# 0_cpu_interface.net
KiCad netlist of a schematic drawn in EAGLE
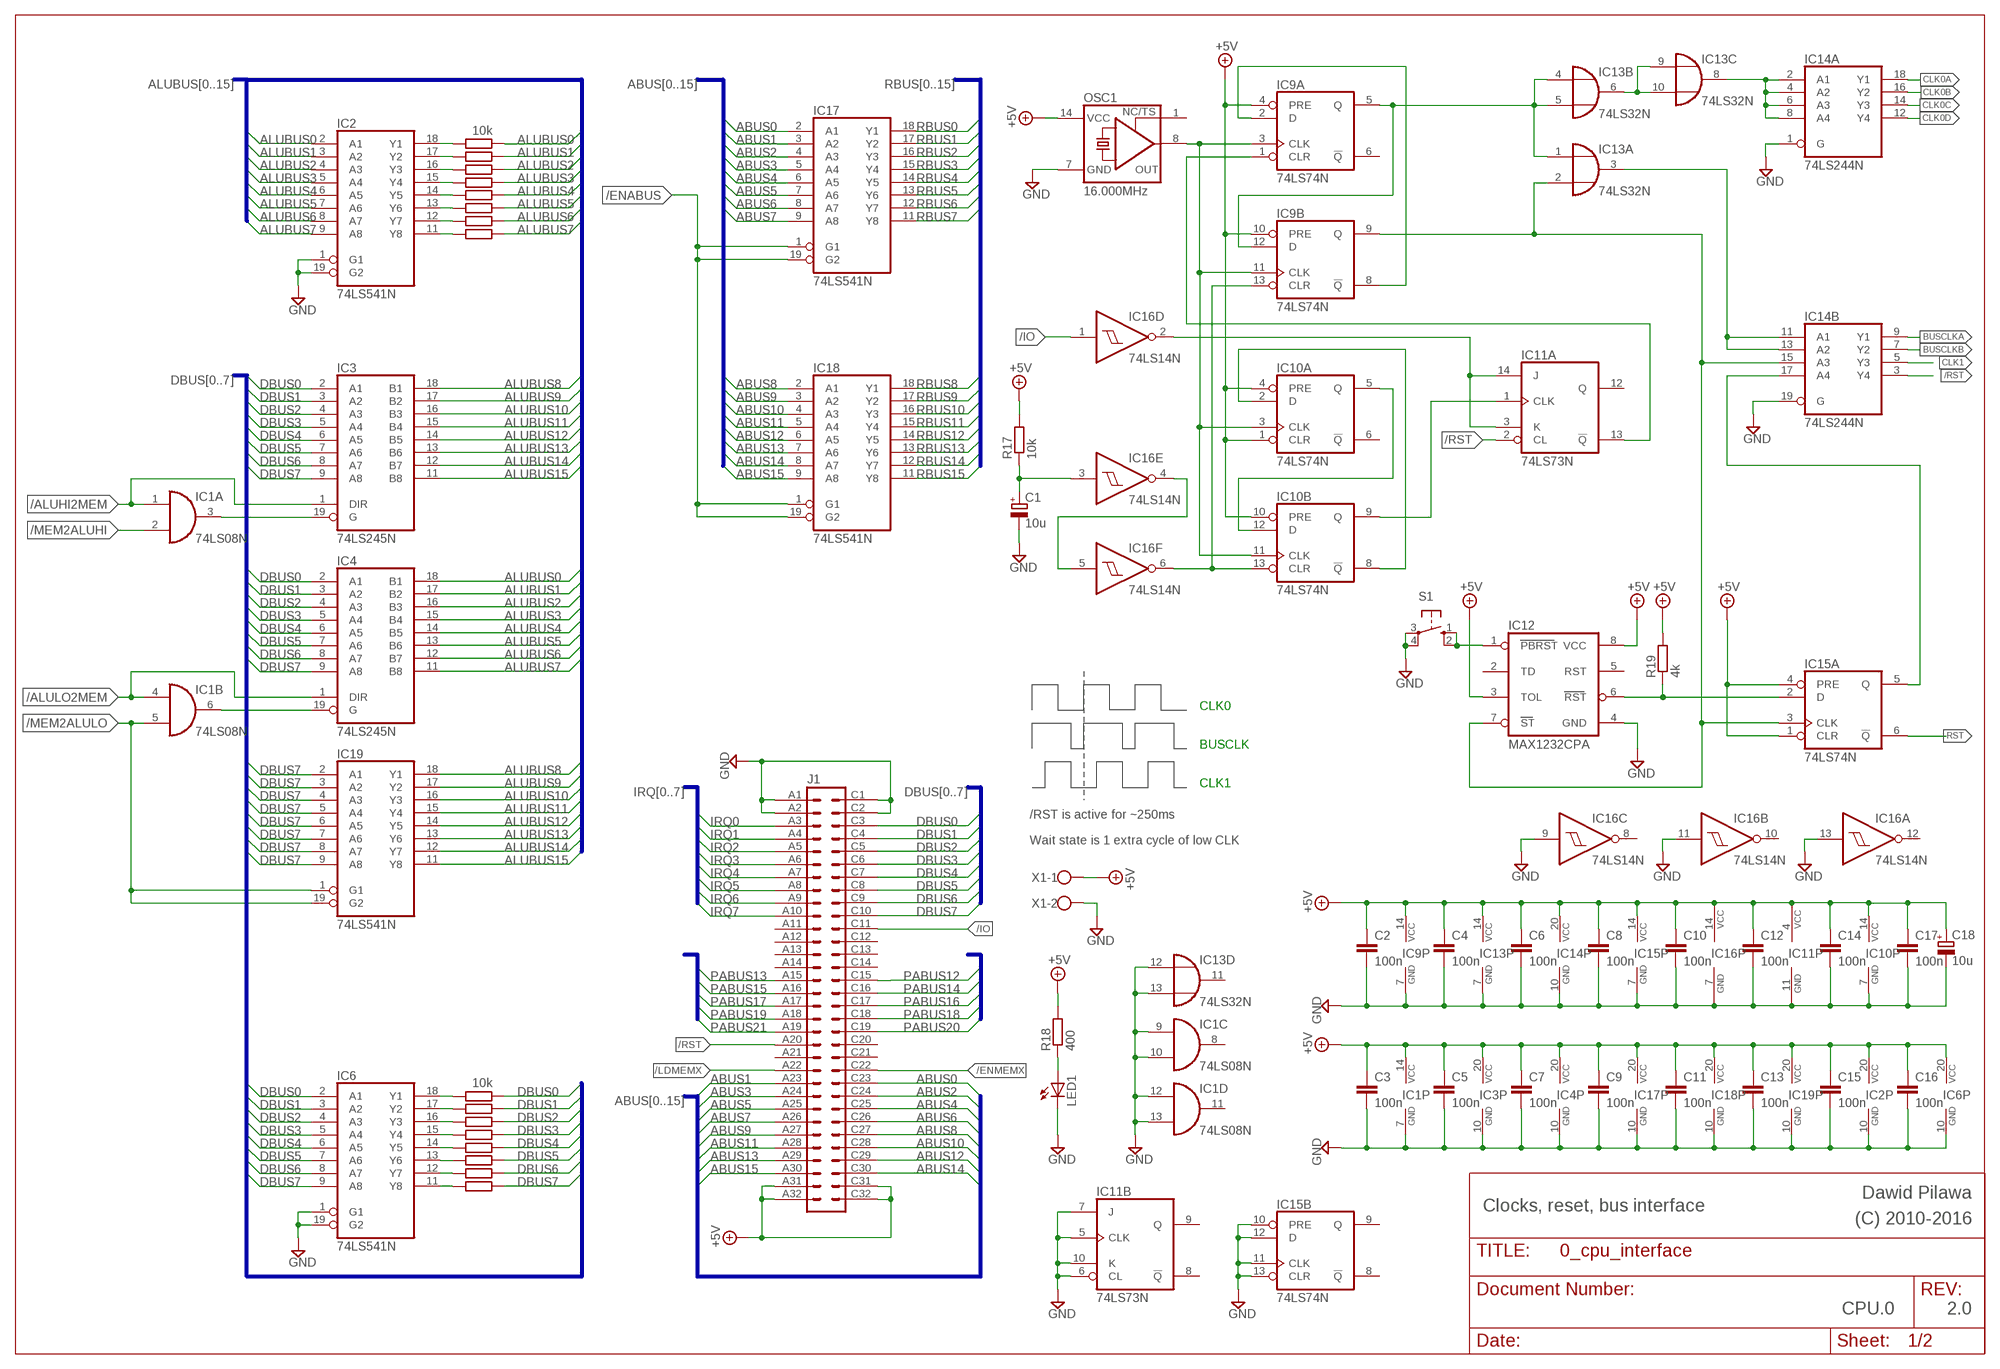
[diagram p0: schematic, sheet 1]
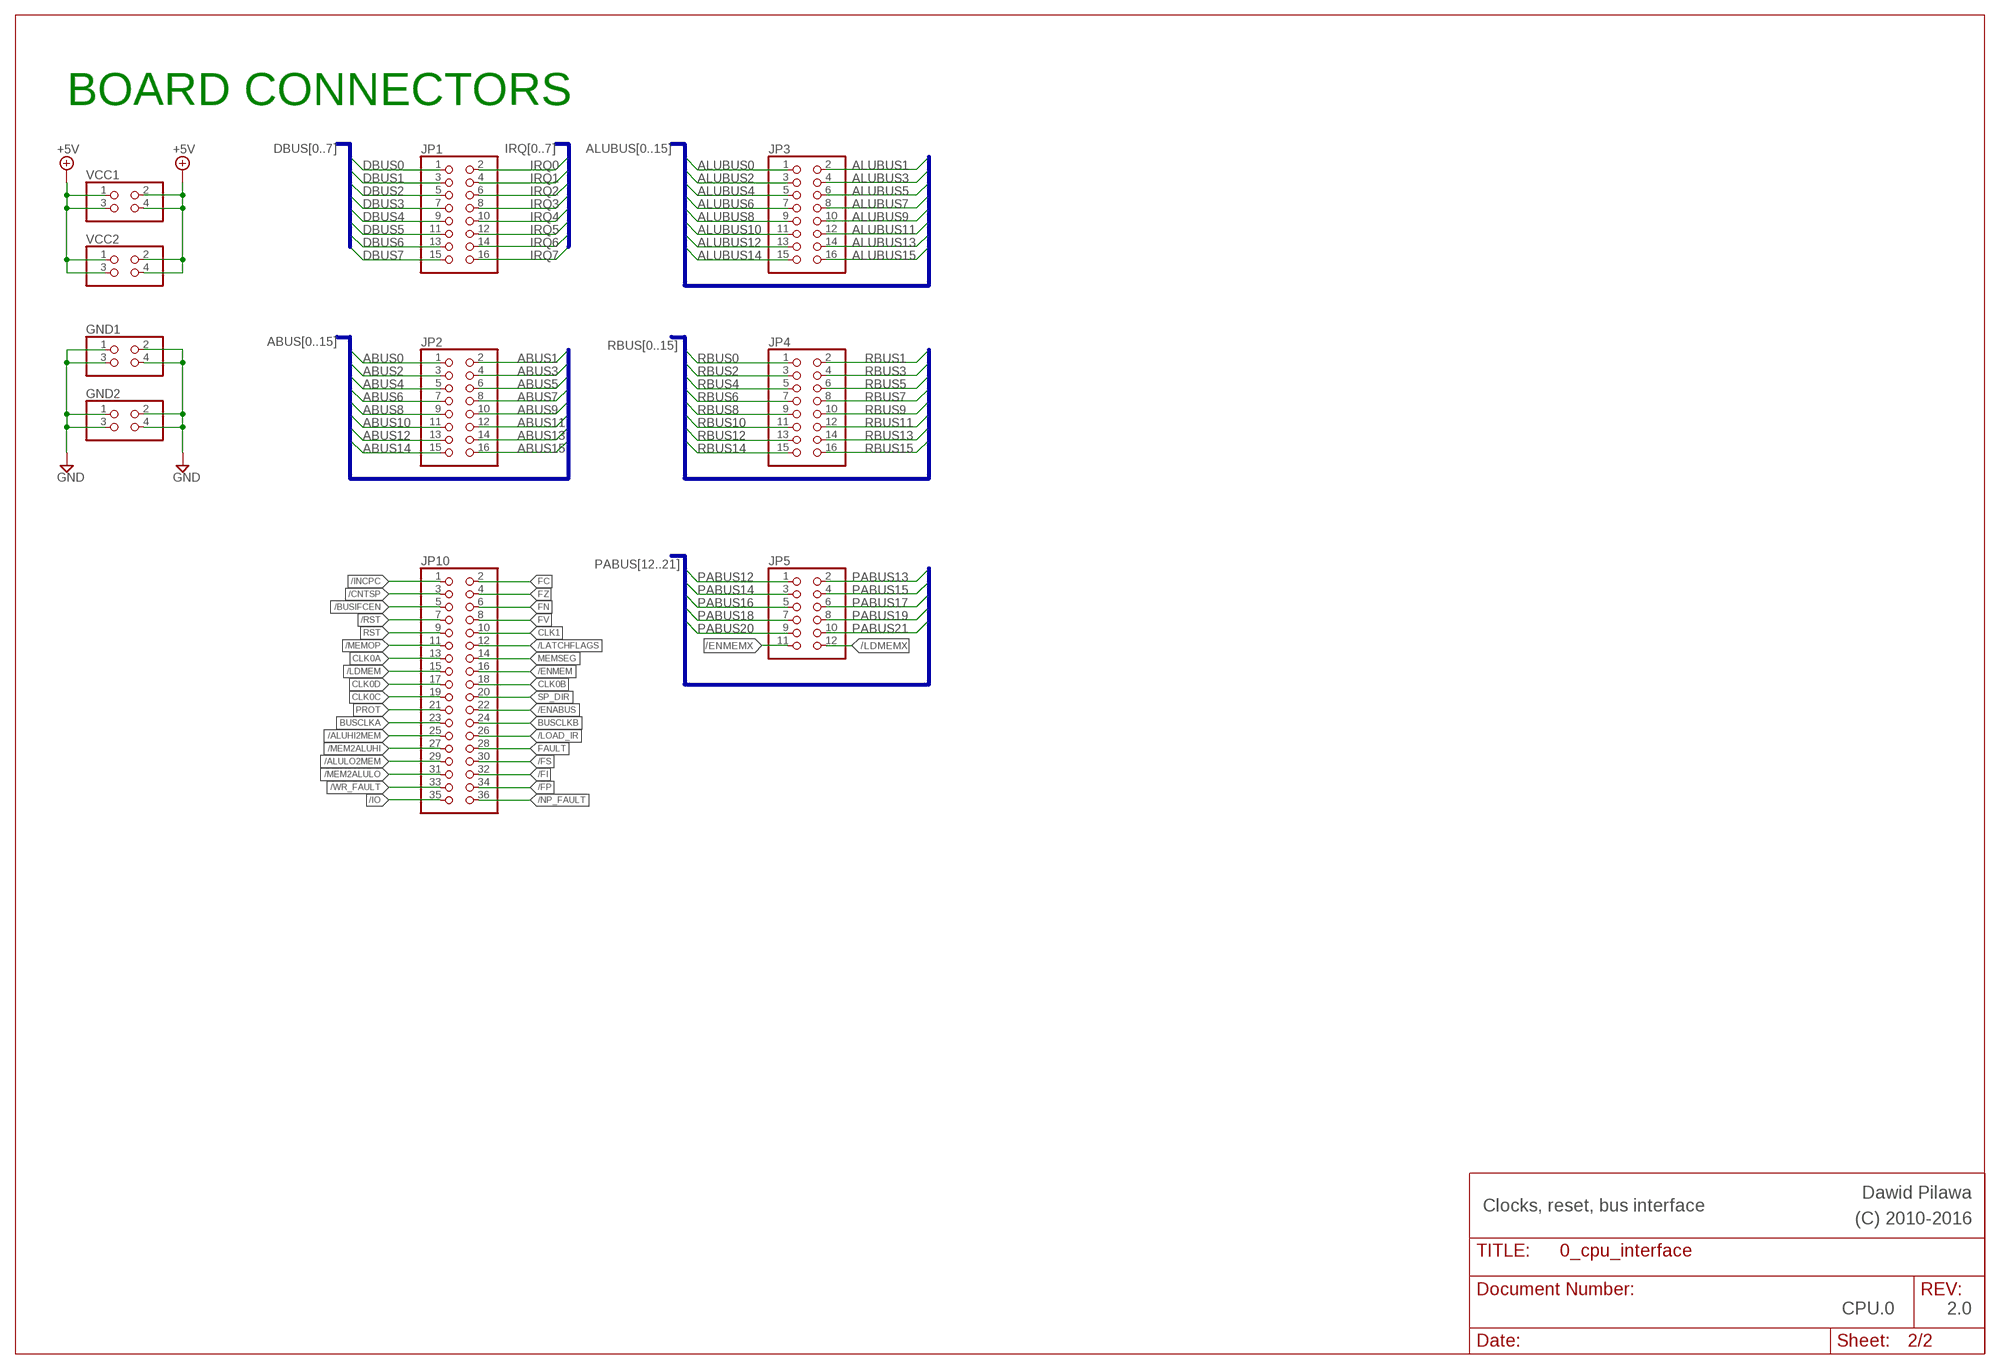
[diagram p1: schematic, sheet 2]

(export (version "E")
  (design (tool "Eeschema 10.0.6"))
  (components
    (comp (ref "C1")
      (value "10u")
      (footprint "eagle-import:E2,5-5")
      (libsource (lib "eagle-import") (part "CPOL-EUE2.5-5"))
    )
    (comp (ref "C2")
      (value "100n")
      (footprint "eagle-import:C050-024X044")
      (libsource (lib "eagle-import") (part "C-EU050-024X044"))
    )
    (comp (ref "C3")
      (value "100n")
      (footprint "eagle-import:C050-024X044")
      (libsource (lib "eagle-import") (part "C-EU050-024X044"))
    )
    (comp (ref "C4")
      (value "100n")
      (footprint "eagle-import:C050-024X044")
      (libsource (lib "eagle-import") (part "C-EU050-024X044"))
    )
    (comp (ref "C5")
      (value "100n")
      (footprint "eagle-import:C050-024X044")
      (libsource (lib "eagle-import") (part "C-EU050-024X044"))
    )
    (comp (ref "C6")
      (value "100n")
      (footprint "eagle-import:C050-024X044")
      (libsource (lib "eagle-import") (part "C-EU050-024X044"))
    )
    (comp (ref "C7")
      (value "100n")
      (footprint "eagle-import:C050-024X044")
      (libsource (lib "eagle-import") (part "C-EU050-024X044"))
    )
    (comp (ref "C8")
      (value "100n")
      (footprint "eagle-import:C050-024X044")
      (libsource (lib "eagle-import") (part "C-EU050-024X044"))
    )
    (comp (ref "C9")
      (value "100n")
      (footprint "eagle-import:C050-024X044")
      (libsource (lib "eagle-import") (part "C-EU050-024X044"))
    )
    (comp (ref "C10")
      (value "100n")
      (footprint "eagle-import:C050-024X044")
      (libsource (lib "eagle-import") (part "C-EU050-024X044"))
    )
    (comp (ref "C11")
      (value "100n")
      (footprint "eagle-import:C050-024X044")
      (libsource (lib "eagle-import") (part "C-EU050-024X044"))
    )
    (comp (ref "C12")
      (value "100n")
      (footprint "eagle-import:C050-024X044")
      (libsource (lib "eagle-import") (part "C-EU050-024X044"))
    )
    (comp (ref "C13")
      (value "100n")
      (footprint "eagle-import:C050-024X044")
      (libsource (lib "eagle-import") (part "C-EU050-024X044"))
    )
    (comp (ref "C14")
      (value "100n")
      (footprint "eagle-import:C050-024X044")
      (libsource (lib "eagle-import") (part "C-EU050-024X044"))
    )
    (comp (ref "C15")
      (value "100n")
      (footprint "eagle-import:C050-024X044")
      (libsource (lib "eagle-import") (part "C-EU050-024X044"))
    )
    (comp (ref "C16")
      (value "100n")
      (footprint "eagle-import:C050-024X044")
      (libsource (lib "eagle-import") (part "C-EU050-024X044"))
    )
    (comp (ref "C17")
      (value "100n")
      (footprint "eagle-import:C050-024X044")
      (libsource (lib "eagle-import") (part "C-EU050-024X044"))
    )
    (comp (ref "C18")
      (value "10u")
      (footprint "eagle-import:E2,5-6")
      (libsource (lib "eagle-import") (part "CPOL-EUE2.5-6"))
    )
    (comp (ref "IC1")
      (value "74LS08N")
      (footprint "eagle-import:DIL14")
      (libsource (lib "eagle-import") (part "7408NLS"))
    )
    (comp (ref "IC2")
      (value "74LS541N")
      (footprint "eagle-import:DIL20")
      (libsource (lib "eagle-import") (part "74541NLS"))
    )
    (comp (ref "IC3")
      (value "74LS245N")
      (footprint "eagle-import:DIL20")
      (libsource (lib "eagle-import") (part "74245NLS"))
    )
    (comp (ref "IC4")
      (value "74LS245N")
      (footprint "eagle-import:DIL20")
      (libsource (lib "eagle-import") (part "74245NLS"))
    )
    (comp (ref "IC6")
      (value "74LS541N")
      (footprint "eagle-import:DIL20")
      (libsource (lib "eagle-import") (part "74541NLS"))
    )
    (comp (ref "IC9")
      (value "74LS74N")
      (footprint "eagle-import:DIL14")
      (libsource (lib "eagle-import") (part "7474NLS"))
    )
    (comp (ref "IC10")
      (value "74LS74N")
      (footprint "eagle-import:DIL14")
      (libsource (lib "eagle-import") (part "7474NLS"))
    )
    (comp (ref "IC11")
      (value "74LS73N")
      (footprint "eagle-import:DIL14")
      (libsource (lib "eagle-import") (part "7473NLS"))
    )
    (comp (ref "IC12")
      (value "MAX1232CPA")
      (footprint "eagle-import:DIL08")
      (libsource (lib "eagle-import") (part "MAX1232CPA"))
    )
    (comp (ref "IC13")
      (value "74LS32N")
      (footprint "eagle-import:DIL14")
      (libsource (lib "eagle-import") (part "7432NLS"))
    )
    (comp (ref "IC14")
      (value "74LS244N")
      (footprint "eagle-import:DIL20")
      (libsource (lib "eagle-import") (part "74244NLS"))
    )
    (comp (ref "IC15")
      (value "74LS74N")
      (footprint "eagle-import:DIL14")
      (libsource (lib "eagle-import") (part "7474NLS"))
    )
    (comp (ref "IC16")
      (value "74LS14N")
      (footprint "eagle-import:DIL14")
      (libsource (lib "eagle-import") (part "7414NLS"))
    )
    (comp (ref "IC17")
      (value "74LS541N")
      (footprint "eagle-import:DIL20")
      (libsource (lib "eagle-import") (part "74541NLS"))
    )
    (comp (ref "IC18")
      (value "74LS541N")
      (footprint "eagle-import:DIL20")
      (libsource (lib "eagle-import") (part "74541NLS"))
    )
    (comp (ref "IC19")
      (value "74LS541N")
      (footprint "eagle-import:DIL20")
      (libsource (lib "eagle-import") (part "74541NLS"))
    )
    (comp (ref "J1")
      (value "VG64B")
      (footprint "eagle-import:VG64B")
      (libsource (lib "eagle-import") (part "VG64B"))
    )
    (comp (ref "LED1")
      (value "LED5MM")
      (footprint "eagle-import:LED5MM")
      (libsource (lib "eagle-import") (part "LED5MM"))
    )
    (comp (ref "OSC1")
      (value "16.000MHz")
      (footprint "eagle-import:DIL14S")
      (libsource (lib "eagle-import") (part "XO-14"))
    )
    (comp (ref "R1")
      (value "10k")
      (footprint "eagle-import:0204_7")
      (libsource (lib "eagle-import") (part "R-EU_0204/7"))
    )
    (comp (ref "R2")
      (value "R-EU_0204/7")
      (footprint "eagle-import:0204_7")
      (libsource (lib "eagle-import") (part "R-EU_0204/7"))
    )
    (comp (ref "R3")
      (value "R-EU_0204/7")
      (footprint "eagle-import:0204_7")
      (libsource (lib "eagle-import") (part "R-EU_0204/7"))
    )
    (comp (ref "R4")
      (value "R-EU_0204/7")
      (footprint "eagle-import:0204_7")
      (libsource (lib "eagle-import") (part "R-EU_0204/7"))
    )
    (comp (ref "R5")
      (value "R-EU_0204/7")
      (footprint "eagle-import:0204_7")
      (libsource (lib "eagle-import") (part "R-EU_0204/7"))
    )
    (comp (ref "R6")
      (value "R-EU_0204/7")
      (footprint "eagle-import:0204_7")
      (libsource (lib "eagle-import") (part "R-EU_0204/7"))
    )
    (comp (ref "R7")
      (value "R-EU_0204/7")
      (footprint "eagle-import:0204_7")
      (libsource (lib "eagle-import") (part "R-EU_0204/7"))
    )
    (comp (ref "R8")
      (value "R-EU_0204/7")
      (footprint "eagle-import:0204_7")
      (libsource (lib "eagle-import") (part "R-EU_0204/7"))
    )
    (comp (ref "R9")
      (value "10k")
      (footprint "eagle-import:0204_7")
      (libsource (lib "eagle-import") (part "R-EU_0204/7"))
    )
    (comp (ref "R10")
      (value "R-EU_0204/7")
      (footprint "eagle-import:0204_7")
      (libsource (lib "eagle-import") (part "R-EU_0204/7"))
    )
    (comp (ref "R11")
      (value "R-EU_0204/7")
      (footprint "eagle-import:0204_7")
      (libsource (lib "eagle-import") (part "R-EU_0204/7"))
    )
    (comp (ref "R12")
      (value "R-EU_0204/7")
      (footprint "eagle-import:0204_7")
      (libsource (lib "eagle-import") (part "R-EU_0204/7"))
    )
    (comp (ref "R13")
      (value "R-EU_0204/7")
      (footprint "eagle-import:0204_7")
      (libsource (lib "eagle-import") (part "R-EU_0204/7"))
    )
    (comp (ref "R14")
      (value "R-EU_0204/7")
      (footprint "eagle-import:0204_7")
      (libsource (lib "eagle-import") (part "R-EU_0204/7"))
    )
    (comp (ref "R15")
      (value "R-EU_0204/7")
      (footprint "eagle-import:0204_7")
      (libsource (lib "eagle-import") (part "R-EU_0204/7"))
    )
    (comp (ref "R16")
      (value "R-EU_0204/7")
      (footprint "eagle-import:0204_7")
      (libsource (lib "eagle-import") (part "R-EU_0204/7"))
    )
    (comp (ref "R17")
      (value "10k")
      (footprint "eagle-import:0204_7")
      (libsource (lib "eagle-import") (part "R-EU_0204/7"))
    )
    (comp (ref "R18")
      (value "400")
      (footprint "eagle-import:0204_7")
      (libsource (lib "eagle-import") (part "R-EU_0204/7"))
    )
    (comp (ref "R19")
      (value "4k")
      (footprint "eagle-import:0204_7")
      (libsource (lib "eagle-import") (part "R-EU_0204/7"))
    )
    (comp (ref "S1")
      (value "10-XX")
      (footprint "eagle-import:B3F-10XX")
      (fields (field (name "MPN") "B3F-1000"))
      (libsource (lib "eagle-import") (part "10-XX"))
    )
    (comp (ref "X1")
      (value "W237-102")
      (footprint "eagle-import:W237-102")
      (fields (field (name "MPN") "237-102"))
      (libsource (lib "eagle-import") (part "W237-102"))
    )
    (comp (ref "GND1")
      (value "PINHD-2X2")
      (footprint "eagle-import:2X02")
      (libsource (lib "eagle-import") (part "PINHD-2X2"))
    )
    (comp (ref "GND2")
      (value "PINHD-2X2")
      (footprint "eagle-import:2X02")
      (libsource (lib "eagle-import") (part "PINHD-2X2"))
    )
    (comp (ref "JP1")
      (value "PINHD-2X8")
      (footprint "eagle-import:2X08")
      (libsource (lib "eagle-import") (part "PINHD-2X8"))
    )
    (comp (ref "JP2")
      (value "PINHD-2X8")
      (footprint "eagle-import:2X08")
      (libsource (lib "eagle-import") (part "PINHD-2X8"))
    )
    (comp (ref "JP3")
      (value "PINHD-2X8")
      (footprint "eagle-import:2X08")
      (libsource (lib "eagle-import") (part "PINHD-2X8"))
    )
    (comp (ref "JP4")
      (value "PINHD-2X8")
      (footprint "eagle-import:2X08")
      (libsource (lib "eagle-import") (part "PINHD-2X8"))
    )
    (comp (ref "JP5")
      (value "PINHD-2X6")
      (footprint "eagle-import:2X06")
      (libsource (lib "eagle-import") (part "PINHD-2X6"))
    )
    (comp (ref "JP10")
      (value "PINHD-2X18")
      (footprint "eagle-import:2X18")
      (libsource (lib "eagle-import") (part "PINHD-2X18"))
    )
    (comp (ref "VCC1")
      (value "PINHD-2X2")
      (footprint "eagle-import:2X02")
      (libsource (lib "eagle-import") (part "PINHD-2X2"))
    )
    (comp (ref "VCC2")
      (value "PINHD-2X2")
      (footprint "eagle-import:2X02")
      (libsource (lib "eagle-import") (part "PINHD-2X2"))
    )
  )
  (nets
    (net (code "1") (name "+5V") (class "Default")
      (node (ref "C10") (pin "1") (pinfunction "1_1") (pintype "passive"))
      (node (ref "C11") (pin "1") (pinfunction "1_1") (pintype "passive"))
      (node (ref "C12") (pin "1") (pinfunction "1_1") (pintype "passive"))
      (node (ref "C13") (pin "1") (pinfunction "1_1") (pintype "passive"))
      (node (ref "C14") (pin "1") (pinfunction "1_1") (pintype "passive"))
      (node (ref "C15") (pin "1") (pinfunction "1_1") (pintype "passive"))
      (node (ref "C16") (pin "1") (pinfunction "1_1") (pintype "passive"))
      (node (ref "C17") (pin "1") (pinfunction "1_1") (pintype "passive"))
      (node (ref "C18") (pin "+") (pinfunction "+_+") (pintype "passive"))
      (node (ref "C2") (pin "1") (pinfunction "1_1") (pintype "passive"))
      (node (ref "C3") (pin "1") (pinfunction "1_1") (pintype "passive"))
      (node (ref "C4") (pin "1") (pinfunction "1_1") (pintype "passive"))
      (node (ref "C5") (pin "1") (pinfunction "1_1") (pintype "passive"))
      (node (ref "C6") (pin "1") (pinfunction "1_1") (pintype "passive"))
      (node (ref "C7") (pin "1") (pinfunction "1_1") (pintype "passive"))
      (node (ref "C8") (pin "1") (pinfunction "1_1") (pintype "passive"))
      (node (ref "C9") (pin "1") (pinfunction "1_1") (pintype "passive"))
      (node (ref "IC1") (pin "14") (pinfunction "VCC_14") (pintype "power_in"))
      (node (ref "IC10") (pin "1") (pinfunction "CLR_1") (pintype "input"))
      (node (ref "IC10") (pin "10") (pinfunction "PRE_10") (pintype "input"))
      (node (ref "IC10") (pin "14") (pinfunction "VCC_14") (pintype "power_in"))
      (node (ref "IC10") (pin "4") (pinfunction "PRE_4") (pintype "input"))
      (node (ref "IC11") (pin "4") (pinfunction "VCC_4") (pintype "power_in"))
      (node (ref "IC12") (pin "3") (pinfunction "TOL_3") (pintype "input"))
      (node (ref "IC12") (pin "8") (pinfunction "VCC_8") (pintype "power_in"))
      (node (ref "IC13") (pin "14") (pinfunction "VCC_14") (pintype "power_in"))
      (node (ref "IC14") (pin "20") (pinfunction "VCC_20") (pintype "power_in"))
      (node (ref "IC15") (pin "1") (pinfunction "CLR_1") (pintype "input"))
      (node (ref "IC15") (pin "14") (pinfunction "VCC_14") (pintype "power_in"))
      (node (ref "IC15") (pin "4") (pinfunction "PRE_4") (pintype "input"))
      (node (ref "IC16") (pin "14") (pinfunction "VCC_14") (pintype "power_in"))
      (node (ref "IC17") (pin "20") (pinfunction "VCC_20") (pintype "power_in"))
      (node (ref "IC18") (pin "20") (pinfunction "VCC_20") (pintype "power_in"))
      (node (ref "IC19") (pin "20") (pinfunction "VCC_20") (pintype "power_in"))
      (node (ref "IC2") (pin "20") (pinfunction "VCC_20") (pintype "power_in"))
      (node (ref "IC3") (pin "20") (pinfunction "VCC_20") (pintype "power_in"))
      (node (ref "IC4") (pin "20") (pinfunction "VCC_20") (pintype "power_in"))
      (node (ref "IC6") (pin "20") (pinfunction "VCC_20") (pintype "power_in"))
      (node (ref "IC9") (pin "10") (pinfunction "PRE_10") (pintype "input"))
      (node (ref "IC9") (pin "14") (pinfunction "VCC_14") (pintype "power_in"))
      (node (ref "IC9") (pin "4") (pinfunction "PRE_4") (pintype "input"))
      (node (ref "J1") (pin "A31") (pinfunction "A31_A31") (pintype "passive"))
      (node (ref "J1") (pin "A32") (pinfunction "A32_A32") (pintype "passive"))
      (node (ref "J1") (pin "C31") (pinfunction "C31_C31") (pintype "passive"))
      (node (ref "J1") (pin "C32") (pinfunction "C32_C32") (pintype "passive"))
      (node (ref "OSC1") (pin "14") (pinfunction "VCC_14") (pintype "power_in"))
      (node (ref "R17") (pin "2") (pinfunction "2_2") (pintype "passive"))
      (node (ref "R18") (pin "2") (pinfunction "2_2") (pintype "passive"))
      (node (ref "R19") (pin "2") (pinfunction "2_2") (pintype "passive"))
      (node (ref "VCC1") (pin "1") (pinfunction "1_1") (pintype "passive"))
      (node (ref "VCC1") (pin "2") (pinfunction "2_2") (pintype "passive"))
      (node (ref "VCC1") (pin "3") (pinfunction "3_3") (pintype "passive"))
      (node (ref "VCC1") (pin "4") (pinfunction "4_4") (pintype "passive"))
      (node (ref "VCC2") (pin "1") (pinfunction "1_1") (pintype "passive"))
      (node (ref "VCC2") (pin "2") (pinfunction "2_2") (pintype "passive"))
      (node (ref "VCC2") (pin "3") (pinfunction "3_3") (pintype "passive"))
      (node (ref "VCC2") (pin "4") (pinfunction "4_4") (pintype "passive"))
      (node (ref "X1") (pin "1") (pinfunction "KL_1") (pintype "passive"))
    )
    (net (code "14") (name "ABUS0") (class "Default")
      (node (ref "IC17") (pin "2") (pinfunction "A1_2") (pintype "input"))
      (node (ref "J1") (pin "C23") (pinfunction "C23_C23") (pintype "passive"))
      (node (ref "JP2") (pin "1") (pinfunction "1_1") (pintype "passive"))
    )
    (net (code "15") (name "ABUS1") (class "Default")
      (node (ref "IC17") (pin "3") (pinfunction "A2_3") (pintype "input"))
      (node (ref "J1") (pin "A23") (pinfunction "A23_A23") (pintype "passive"))
      (node (ref "JP2") (pin "2") (pinfunction "2_2") (pintype "passive"))
    )
    (net (code "16") (name "ABUS2") (class "Default")
      (node (ref "IC17") (pin "4") (pinfunction "A3_4") (pintype "input"))
      (node (ref "J1") (pin "C24") (pinfunction "C24_C24") (pintype "passive"))
      (node (ref "JP2") (pin "3") (pinfunction "3_3") (pintype "passive"))
    )
    (net (code "17") (name "ABUS3") (class "Default")
      (node (ref "IC17") (pin "5") (pinfunction "A4_5") (pintype "input"))
      (node (ref "J1") (pin "A24") (pinfunction "A24_A24") (pintype "passive"))
      (node (ref "JP2") (pin "4") (pinfunction "4_4") (pintype "passive"))
    )
    (net (code "18") (name "ABUS4") (class "Default")
      (node (ref "IC17") (pin "6") (pinfunction "A5_6") (pintype "input"))
      (node (ref "J1") (pin "C25") (pinfunction "C25_C25") (pintype "passive"))
      (node (ref "JP2") (pin "5") (pinfunction "5_5") (pintype "passive"))
    )
    (net (code "19") (name "ABUS5") (class "Default")
      (node (ref "IC17") (pin "7") (pinfunction "A6_7") (pintype "input"))
      (node (ref "J1") (pin "A25") (pinfunction "A25_A25") (pintype "passive"))
      (node (ref "JP2") (pin "6") (pinfunction "6_6") (pintype "passive"))
    )
    (net (code "20") (name "ABUS6") (class "Default")
      (node (ref "IC17") (pin "8") (pinfunction "A7_8") (pintype "input"))
      (node (ref "J1") (pin "C26") (pinfunction "C26_C26") (pintype "passive"))
      (node (ref "JP2") (pin "7") (pinfunction "7_7") (pintype "passive"))
    )
    (net (code "21") (name "ABUS7") (class "Default")
      (node (ref "IC17") (pin "9") (pinfunction "A8_9") (pintype "input"))
      (node (ref "J1") (pin "A26") (pinfunction "A26_A26") (pintype "passive"))
      (node (ref "JP2") (pin "8") (pinfunction "8_8") (pintype "passive"))
    )
    (net (code "22") (name "ABUS8") (class "Default")
      (node (ref "IC18") (pin "2") (pinfunction "A1_2") (pintype "input"))
      (node (ref "J1") (pin "C27") (pinfunction "C27_C27") (pintype "passive"))
      (node (ref "JP2") (pin "9") (pinfunction "9_9") (pintype "passive"))
    )
    (net (code "23") (name "ABUS9") (class "Default")
      (node (ref "IC18") (pin "3") (pinfunction "A2_3") (pintype "input"))
      (node (ref "J1") (pin "A27") (pinfunction "A27_A27") (pintype "passive"))
      (node (ref "JP2") (pin "10") (pinfunction "10_10") (pintype "passive"))
    )
    (net (code "24") (name "ABUS10") (class "Default")
      (node (ref "IC18") (pin "4") (pinfunction "A3_4") (pintype "input"))
      (node (ref "J1") (pin "C28") (pinfunction "C28_C28") (pintype "passive"))
      (node (ref "JP2") (pin "11") (pinfunction "11_11") (pintype "passive"))
    )
    (net (code "25") (name "ABUS11") (class "Default")
      (node (ref "IC18") (pin "5") (pinfunction "A4_5") (pintype "input"))
      (node (ref "J1") (pin "A28") (pinfunction "A28_A28") (pintype "passive"))
      (node (ref "JP2") (pin "12") (pinfunction "12_12") (pintype "passive"))
    )
    (net (code "26") (name "ABUS12") (class "Default")
      (node (ref "IC18") (pin "6") (pinfunction "A5_6") (pintype "input"))
      (node (ref "J1") (pin "C29") (pinfunction "C29_C29") (pintype "passive"))
      (node (ref "JP2") (pin "13") (pinfunction "13_13") (pintype "passive"))
    )
    (net (code "27") (name "ABUS13") (class "Default")
      (node (ref "IC18") (pin "7") (pinfunction "A6_7") (pintype "input"))
      (node (ref "J1") (pin "A29") (pinfunction "A29_A29") (pintype "passive"))
      (node (ref "JP2") (pin "14") (pinfunction "14_14") (pintype "passive"))
    )
    (net (code "28") (name "ABUS14") (class "Default")
      (node (ref "IC18") (pin "8") (pinfunction "A7_8") (pintype "input"))
      (node (ref "J1") (pin "C30") (pinfunction "C30_C30") (pintype "passive"))
      (node (ref "JP2") (pin "15") (pinfunction "15_15") (pintype "passive"))
    )
    (net (code "29") (name "ABUS15") (class "Default")
      (node (ref "IC18") (pin "9") (pinfunction "A8_9") (pintype "input"))
      (node (ref "J1") (pin "A30") (pinfunction "A30_A30") (pintype "passive"))
      (node (ref "JP2") (pin "16") (pinfunction "16_16") (pintype "passive"))
    )
    (net (code "30") (name "ALUBUS0") (class "Default")
      (node (ref "IC2") (pin "2") (pinfunction "A1_2") (pintype "input"))
      (node (ref "IC4") (pin "18") (pinfunction "B1_18") (pintype "bidirectional"))
      (node (ref "JP3") (pin "1") (pinfunction "1_1") (pintype "passive"))
      (node (ref "R1") (pin "2") (pinfunction "2_2") (pintype "passive"))
    )
    (net (code "31") (name "ALUBUS1") (class "Default")
      (node (ref "IC2") (pin "3") (pinfunction "A2_3") (pintype "input"))
      (node (ref "IC4") (pin "17") (pinfunction "B2_17") (pintype "bidirectional"))
      (node (ref "JP3") (pin "2") (pinfunction "2_2") (pintype "passive"))
      (node (ref "R2") (pin "2") (pinfunction "2_2") (pintype "passive"))
    )
    (net (code "32") (name "ALUBUS2") (class "Default")
      (node (ref "IC2") (pin "4") (pinfunction "A3_4") (pintype "input"))
      (node (ref "IC4") (pin "16") (pinfunction "B3_16") (pintype "bidirectional"))
      (node (ref "JP3") (pin "3") (pinfunction "3_3") (pintype "passive"))
      (node (ref "R3") (pin "2") (pinfunction "2_2") (pintype "passive"))
    )
    (net (code "33") (name "ALUBUS3") (class "Default")
      (node (ref "IC2") (pin "5") (pinfunction "A4_5") (pintype "input"))
      (node (ref "IC4") (pin "15") (pinfunction "B4_15") (pintype "bidirectional"))
      (node (ref "JP3") (pin "4") (pinfunction "4_4") (pintype "passive"))
      (node (ref "R4") (pin "2") (pinfunction "2_2") (pintype "passive"))
    )
    (net (code "34") (name "ALUBUS4") (class "Default")
      (node (ref "IC2") (pin "6") (pinfunction "A5_6") (pintype "input"))
      (node (ref "IC4") (pin "14") (pinfunction "B5_14") (pintype "bidirectional"))
      (node (ref "JP3") (pin "5") (pinfunction "5_5") (pintype "passive"))
      (node (ref "R5") (pin "2") (pinfunction "2_2") (pintype "passive"))
    )
    (net (code "35") (name "ALUBUS5") (class "Default")
      (node (ref "IC2") (pin "7") (pinfunction "A6_7") (pintype "input"))
      (node (ref "IC4") (pin "13") (pinfunction "B6_13") (pintype "bidirectional"))
      (node (ref "JP3") (pin "6") (pinfunction "6_6") (pintype "passive"))
      (node (ref "R6") (pin "2") (pinfunction "2_2") (pintype "passive"))
    )
    (net (code "36") (name "ALUBUS6") (class "Default")
      (node (ref "IC2") (pin "8") (pinfunction "A7_8") (pintype "input"))
      (node (ref "IC4") (pin "12") (pinfunction "B7_12") (pintype "bidirectional"))
      (node (ref "JP3") (pin "7") (pinfunction "7_7") (pintype "passive"))
      (node (ref "R7") (pin "2") (pinfunction "2_2") (pintype "passive"))
    )
    (net (code "37") (name "ALUBUS7") (class "Default")
      (node (ref "IC2") (pin "9") (pinfunction "A8_9") (pintype "input"))
      (node (ref "IC4") (pin "11") (pinfunction "B8_11") (pintype "bidirectional"))
      (node (ref "JP3") (pin "8") (pinfunction "8_8") (pintype "passive"))
      (node (ref "R8") (pin "2") (pinfunction "2_2") (pintype "passive"))
    )
    (net (code "38") (name "ALUBUS8") (class "Default")
      (node (ref "IC19") (pin "18") (pinfunction "Y1_18") (pintype "tri_state"))
      (node (ref "IC3") (pin "18") (pinfunction "B1_18") (pintype "bidirectional"))
      (node (ref "JP3") (pin "9") (pinfunction "9_9") (pintype "passive"))
    )
    (net (code "39") (name "ALUBUS9") (class "Default")
      (node (ref "IC19") (pin "17") (pinfunction "Y2_17") (pintype "tri_state"))
      (node (ref "IC3") (pin "17") (pinfunction "B2_17") (pintype "bidirectional"))
      (node (ref "JP3") (pin "10") (pinfunction "10_10") (pintype "passive"))
    )
    (net (code "40") (name "ALUBUS10") (class "Default")
      (node (ref "IC19") (pin "16") (pinfunction "Y3_16") (pintype "tri_state"))
      (node (ref "IC3") (pin "16") (pinfunction "B3_16") (pintype "bidirectional"))
      (node (ref "JP3") (pin "11") (pinfunction "11_11") (pintype "passive"))
    )
    (net (code "41") (name "ALUBUS11") (class "Default")
      (node (ref "IC19") (pin "15") (pinfunction "Y4_15") (pintype "tri_state"))
      (node (ref "IC3") (pin "15") (pinfunction "B4_15") (pintype "bidirectional"))
      (node (ref "JP3") (pin "12") (pinfunction "12_12") (pintype "passive"))
    )
    (net (code "42") (name "ALUBUS12") (class "Default")
      (node (ref "IC19") (pin "14") (pinfunction "Y5_14") (pintype "tri_state"))
      (node (ref "IC3") (pin "14") (pinfunction "B5_14") (pintype "bidirectional"))
      (node (ref "JP3") (pin "13") (pinfunction "13_13") (pintype "passive"))
    )
    (net (code "43") (name "ALUBUS13") (class "Default")
      (node (ref "IC19") (pin "13") (pinfunction "Y6_13") (pintype "tri_state"))
      (node (ref "IC3") (pin "13") (pinfunction "B6_13") (pintype "bidirectional"))
      (node (ref "JP3") (pin "14") (pinfunction "14_14") (pintype "passive"))
    )
    (net (code "44") (name "ALUBUS14") (class "Default")
      (node (ref "IC19") (pin "12") (pinfunction "Y7_12") (pintype "tri_state"))
      (node (ref "IC3") (pin "12") (pinfunction "B7_12") (pintype "bidirectional"))
      (node (ref "JP3") (pin "15") (pinfunction "15_15") (pintype "passive"))
    )
    (net (code "45") (name "ALUBUS15") (class "Default")
      (node (ref "IC19") (pin "11") (pinfunction "Y8_11") (pintype "tri_state"))
      (node (ref "IC3") (pin "11") (pinfunction "B8_11") (pintype "bidirectional"))
      (node (ref "JP3") (pin "16") (pinfunction "16_16") (pintype "passive"))
    )
    (net (code "46") (name "BUSCLKA") (class "Default")
      (node (ref "IC14") (pin "9") (pinfunction "Y1_9") (pintype "tri_state"))
      (node (ref "JP10") (pin "23") (pinfunction "23_23") (pintype "passive"))
    )
    (net (code "47") (name "BUSCLKB") (class "Default")
      (node (ref "IC14") (pin "7") (pinfunction "Y2_7") (pintype "tri_state"))
      (node (ref "JP10") (pin "24") (pinfunction "24_24") (pintype "passive"))
    )
    (net (code "48") (name "CLK0A") (class "Default")
      (node (ref "IC14") (pin "18") (pinfunction "Y1_18") (pintype "tri_state"))
      (node (ref "JP10") (pin "13") (pinfunction "13_13") (pintype "passive"))
    )
    (net (code "49") (name "CLK0B") (class "Default")
      (node (ref "IC14") (pin "16") (pinfunction "Y2_16") (pintype "tri_state"))
      (node (ref "JP10") (pin "18") (pinfunction "18_18") (pintype "passive"))
    )
    (net (code "50") (name "CLK0C") (class "Default")
      (node (ref "IC14") (pin "14") (pinfunction "Y3_14") (pintype "tri_state"))
      (node (ref "JP10") (pin "19") (pinfunction "19_19") (pintype "passive"))
    )
    (net (code "51") (name "CLK0D") (class "Default")
      (node (ref "IC14") (pin "12") (pinfunction "Y4_12") (pintype "tri_state"))
      (node (ref "JP10") (pin "17") (pinfunction "17_17") (pintype "passive"))
    )
    (net (code "52") (name "CLK1") (class "Default")
      (node (ref "IC14") (pin "5") (pinfunction "Y3_5") (pintype "tri_state"))
      (node (ref "JP10") (pin "10") (pinfunction "10_10") (pintype "passive"))
    )
    (net (code "53") (name "DBUS0") (class "Default")
      (node (ref "IC3") (pin "2") (pinfunction "A1_2") (pintype "bidirectional"))
      (node (ref "IC4") (pin "2") (pinfunction "A1_2") (pintype "bidirectional"))
      (node (ref "IC6") (pin "2") (pinfunction "A1_2") (pintype "input"))
      (node (ref "J1") (pin "C3") (pinfunction "C3_C3") (pintype "passive"))
      (node (ref "JP1") (pin "1") (pinfunction "1_1") (pintype "passive"))
      (node (ref "R9") (pin "2") (pinfunction "2_2") (pintype "passive"))
    )
    (net (code "54") (name "DBUS1") (class "Default")
      (node (ref "IC3") (pin "3") (pinfunction "A2_3") (pintype "bidirectional"))
      (node (ref "IC4") (pin "3") (pinfunction "A2_3") (pintype "bidirectional"))
      (node (ref "IC6") (pin "3") (pinfunction "A2_3") (pintype "input"))
      (node (ref "J1") (pin "C4") (pinfunction "C4_C4") (pintype "passive"))
      (node (ref "JP1") (pin "3") (pinfunction "3_3") (pintype "passive"))
      (node (ref "R10") (pin "2") (pinfunction "2_2") (pintype "passive"))
    )
    (net (code "55") (name "DBUS2") (class "Default")
      (node (ref "IC3") (pin "4") (pinfunction "A3_4") (pintype "bidirectional"))
      (node (ref "IC4") (pin "4") (pinfunction "A3_4") (pintype "bidirectional"))
      (node (ref "IC6") (pin "4") (pinfunction "A3_4") (pintype "input"))
      (node (ref "J1") (pin "C5") (pinfunction "C5_C5") (pintype "passive"))
      (node (ref "JP1") (pin "5") (pinfunction "5_5") (pintype "passive"))
      (node (ref "R11") (pin "2") (pinfunction "2_2") (pintype "passive"))
    )
    (net (code "56") (name "DBUS3") (class "Default")
      (node (ref "IC3") (pin "5") (pinfunction "A4_5") (pintype "bidirectional"))
      (node (ref "IC4") (pin "5") (pinfunction "A4_5") (pintype "bidirectional"))
      (node (ref "IC6") (pin "5") (pinfunction "A4_5") (pintype "input"))
      (node (ref "J1") (pin "C6") (pinfunction "C6_C6") (pintype "passive"))
      (node (ref "JP1") (pin "7") (pinfunction "7_7") (pintype "passive"))
      (node (ref "R12") (pin "2") (pinfunction "2_2") (pintype "passive"))
    )
    (net (code "57") (name "DBUS4") (class "Default")
      (node (ref "IC3") (pin "6") (pinfunction "A5_6") (pintype "bidirectional"))
      (node (ref "IC4") (pin "6") (pinfunction "A5_6") (pintype "bidirectional"))
      (node (ref "IC6") (pin "6") (pinfunction "A5_6") (pintype "input"))
      (node (ref "J1") (pin "C7") (pinfunction "C7_C7") (pintype "passive"))
      (node (ref "JP1") (pin "9") (pinfunction "9_9") (pintype "passive"))
      (node (ref "R13") (pin "2") (pinfunction "2_2") (pintype "passive"))
    )
    (net (code "58") (name "DBUS5") (class "Default")
      (node (ref "IC3") (pin "7") (pinfunction "A6_7") (pintype "bidirectional"))
      (node (ref "IC4") (pin "7") (pinfunction "A6_7") (pintype "bidirectional"))
      (node (ref "IC6") (pin "7") (pinfunction "A6_7") (pintype "input"))
      (node (ref "J1") (pin "C8") (pinfunction "C8_C8") (pintype "passive"))
      (node (ref "JP1") (pin "11") (pinfunction "11_11") (pintype "passive"))
      (node (ref "R14") (pin "2") (pinfunction "2_2") (pintype "passive"))
    )
    (net (code "59") (name "DBUS6") (class "Default")
      (node (ref "IC3") (pin "8") (pinfunction "A7_8") (pintype "bidirectional"))
      (node (ref "IC4") (pin "8") (pinfunction "A7_8") (pintype "bidirectional"))
      (node (ref "IC6") (pin "8") (pinfunction "A7_8") (pintype "input"))
      (node (ref "J1") (pin "C9") (pinfunction "C9_C9") (pintype "passive"))
      (node (ref "JP1") (pin "13") (pinfunction "13_13") (pintype "passive"))
      (node (ref "R15") (pin "2") (pinfunction "2_2") (pintype "passive"))
    )
    (net (code "60") (name "DBUS7") (class "Default")
      (node (ref "IC19") (pin "2") (pinfunction "A1_2") (pintype "input"))
      (node (ref "IC19") (pin "3") (pinfunction "A2_3") (pintype "input"))
      (node (ref "IC19") (pin "4") (pinfunction "A3_4") (pintype "input"))
      (node (ref "IC19") (pin "5") (pinfunction "A4_5") (pintype "input"))
      (node (ref "IC19") (pin "6") (pinfunction "A5_6") (pintype "input"))
      (node (ref "IC19") (pin "7") (pinfunction "A6_7") (pintype "input"))
      (node (ref "IC19") (pin "8") (pinfunction "A7_8") (pintype "input"))
      (node (ref "IC19") (pin "9") (pinfunction "A8_9") (pintype "input"))
      (node (ref "IC3") (pin "9") (pinfunction "A8_9") (pintype "bidirectional"))
      (node (ref "IC4") (pin "9") (pinfunction "A8_9") (pintype "bidirectional"))
      (node (ref "IC6") (pin "9") (pinfunction "A8_9") (pintype "input"))
      (node (ref "J1") (pin "C10") (pinfunction "C10_C10") (pintype "passive"))
      (node (ref "JP1") (pin "15") (pinfunction "15_15") (pintype "passive"))
      (node (ref "R16") (pin "2") (pinfunction "2_2") (pintype "passive"))
    )
    (net (code "61") (name "FAULT") (class "Default")
      (node (ref "JP10") (pin "28") (pinfunction "28_28") (pintype "passive"))
    )
    (net (code "62") (name "FC") (class "Default")
      (node (ref "JP10") (pin "2") (pinfunction "2_2") (pintype "passive"))
    )
    (net (code "63") (name "FN") (class "Default")
      (node (ref "JP10") (pin "6") (pinfunction "6_6") (pintype "passive"))
    )
    (net (code "64") (name "FV") (class "Default")
      (node (ref "JP10") (pin "8") (pinfunction "8_8") (pintype "passive"))
    )
    (net (code "65") (name "FZ") (class "Default")
      (node (ref "JP10") (pin "4") (pinfunction "4_4") (pintype "passive"))
    )
    (net (code "66") (name "GND") (class "Default")
      (node (ref "C1") (pin "-") (pinfunction "-_-") (pintype "passive"))
      (node (ref "C10") (pin "2") (pinfunction "2_2") (pintype "passive"))
      (node (ref "C11") (pin "2") (pinfunction "2_2") (pintype "passive"))
      (node (ref "C12") (pin "2") (pinfunction "2_2") (pintype "passive"))
      (node (ref "C13") (pin "2") (pinfunction "2_2") (pintype "passive"))
      (node (ref "C14") (pin "2") (pinfunction "2_2") (pintype "passive"))
      (node (ref "C15") (pin "2") (pinfunction "2_2") (pintype "passive"))
      (node (ref "C16") (pin "2") (pinfunction "2_2") (pintype "passive"))
      (node (ref "C17") (pin "2") (pinfunction "2_2") (pintype "passive"))
      (node (ref "C18") (pin "-") (pinfunction "-_-") (pintype "passive"))
      (node (ref "C2") (pin "2") (pinfunction "2_2") (pintype "passive"))
      (node (ref "C3") (pin "2") (pinfunction "2_2") (pintype "passive"))
      (node (ref "C4") (pin "2") (pinfunction "2_2") (pintype "passive"))
      (node (ref "C5") (pin "2") (pinfunction "2_2") (pintype "passive"))
      (node (ref "C6") (pin "2") (pinfunction "2_2") (pintype "passive"))
      (node (ref "C7") (pin "2") (pinfunction "2_2") (pintype "passive"))
      (node (ref "C8") (pin "2") (pinfunction "2_2") (pintype "passive"))
      (node (ref "C9") (pin "2") (pinfunction "2_2") (pintype "passive"))
      (node (ref "GND1") (pin "1") (pinfunction "1_1") (pintype "passive"))
      (node (ref "GND1") (pin "2") (pinfunction "2_2") (pintype "passive"))
      (node (ref "GND1") (pin "3") (pinfunction "3_3") (pintype "passive"))
      (node (ref "GND1") (pin "4") (pinfunction "4_4") (pintype "passive"))
      (node (ref "GND2") (pin "1") (pinfunction "1_1") (pintype "passive"))
      (node (ref "GND2") (pin "2") (pinfunction "2_2") (pintype "passive"))
      (node (ref "GND2") (pin "3") (pinfunction "3_3") (pintype "passive"))
      (node (ref "GND2") (pin "4") (pinfunction "4_4") (pintype "passive"))
      (node (ref "IC1") (pin "10") (pinfunction "I1_10") (pintype "input"))
      (node (ref "IC1") (pin "12") (pinfunction "I0_12") (pintype "input"))
      (node (ref "IC1") (pin "13") (pinfunction "I1_13") (pintype "input"))
      (node (ref "IC1") (pin "7") (pinfunction "GND_7") (pintype "power_in"))
      (node (ref "IC1") (pin "9") (pinfunction "I0_9") (pintype "input"))
      (node (ref "IC10") (pin "7") (pinfunction "GND_7") (pintype "power_in"))
      (node (ref "IC11") (pin "10") (pinfunction "K_10") (pintype "input"))
      (node (ref "IC11") (pin "11") (pinfunction "GND_11") (pintype "power_in"))
      (node (ref "IC11") (pin "5") (pinfunction "CLK_5") (pintype "input"))
      (node (ref "IC11") (pin "6") (pinfunction "CL_6") (pintype "input"))
      (node (ref "IC11") (pin "7") (pinfunction "J_7") (pintype "input"))
      (node (ref "IC12") (pin "4") (pinfunction "GND_4") (pintype "power_in"))
      (node (ref "IC13") (pin "12") (pinfunction "I0_12") (pintype "input"))
      (node (ref "IC13") (pin "13") (pinfunction "I1_13") (pintype "input"))
      (node (ref "IC13") (pin "7") (pinfunction "GND_7") (pintype "power_in"))
      (node (ref "IC14") (pin "1") (pinfunction "G_1") (pintype "input"))
      (node (ref "IC14") (pin "10") (pinfunction "GND_10") (pintype "power_in"))
      (node (ref "IC14") (pin "19") (pinfunction "G_19") (pintype "input"))
      (node (ref "IC15") (pin "10") (pinfunction "PRE_10") (pintype "input"))
      (node (ref "IC15") (pin "11") (pinfunction "CLK_11") (pintype "input"))
      (node (ref "IC15") (pin "12") (pinfunction "D_12") (pintype "input"))
      (node (ref "IC15") (pin "13") (pinfunction "CLR_13") (pintype "input"))
      (node (ref "IC15") (pin "7") (pinfunction "GND_7") (pintype "power_in"))
      (node (ref "IC16") (pin "11") (pinfunction "I_11") (pintype "input"))
      (node (ref "IC16") (pin "13") (pinfunction "I_13") (pintype "input"))
      (node (ref "IC16") (pin "7") (pinfunction "GND_7") (pintype "power_in"))
      (node (ref "IC16") (pin "9") (pinfunction "I_9") (pintype "input"))
      (node (ref "IC17") (pin "10") (pinfunction "GND_10") (pintype "power_in"))
      (node (ref "IC18") (pin "10") (pinfunction "GND_10") (pintype "power_in"))
      (node (ref "IC19") (pin "10") (pinfunction "GND_10") (pintype "power_in"))
      (node (ref "IC2") (pin "1") (pinfunction "G1_1") (pintype "input"))
      (node (ref "IC2") (pin "10") (pinfunction "GND_10") (pintype "power_in"))
      (node (ref "IC2") (pin "19") (pinfunction "G2_19") (pintype "input"))
      (node (ref "IC3") (pin "10") (pinfunction "GND_10") (pintype "power_in"))
      (node (ref "IC4") (pin "10") (pinfunction "GND_10") (pintype "power_in"))
      (node (ref "IC6") (pin "1") (pinfunction "G1_1") (pintype "input"))
      (node (ref "IC6") (pin "10") (pinfunction "GND_10") (pintype "power_in"))
      (node (ref "IC6") (pin "19") (pinfunction "G2_19") (pintype "input"))
      (node (ref "IC9") (pin "7") (pinfunction "GND_7") (pintype "power_in"))
      (node (ref "J1") (pin "A1") (pinfunction "A1_A1") (pintype "passive"))
      (node (ref "J1") (pin "A2") (pinfunction "A2_A2") (pintype "passive"))
      (node (ref "J1") (pin "C1") (pinfunction "C1_C1") (pintype "passive"))
      (node (ref "J1") (pin "C2") (pinfunction "C2_C2") (pintype "passive"))
      (node (ref "LED1") (pin "K") (pinfunction "C_K") (pintype "passive"))
      (node (ref "OSC1") (pin "7") (pinfunction "GND_7") (pintype "power_in"))
      (node (ref "S1") (pin "3") (pinfunction "P_3") (pintype "passive"))
      (node (ref "S1") (pin "4") (pinfunction "P1_4") (pintype "passive"))
      (node (ref "X1") (pin "2") (pinfunction "KL_2") (pintype "passive"))
    )
    (net (code "67") (name "IRQ0") (class "Default")
      (node (ref "J1") (pin "A3") (pinfunction "A3_A3") (pintype "passive"))
      (node (ref "JP1") (pin "2") (pinfunction "2_2") (pintype "passive"))
    )
    (net (code "68") (name "IRQ1") (class "Default")
      (node (ref "J1") (pin "A4") (pinfunction "A4_A4") (pintype "passive"))
      (node (ref "JP1") (pin "4") (pinfunction "4_4") (pintype "passive"))
    )
    (net (code "69") (name "IRQ2") (class "Default")
      (node (ref "J1") (pin "A5") (pinfunction "A5_A5") (pintype "passive"))
      (node (ref "JP1") (pin "6") (pinfunction "6_6") (pintype "passive"))
    )
    (net (code "70") (name "IRQ3") (class "Default")
      (node (ref "J1") (pin "A6") (pinfunction "A6_A6") (pintype "passive"))
      (node (ref "JP1") (pin "8") (pinfunction "8_8") (pintype "passive"))
    )
    (net (code "71") (name "IRQ4") (class "Default")
      (node (ref "J1") (pin "A7") (pinfunction "A7_A7") (pintype "passive"))
      (node (ref "JP1") (pin "10") (pinfunction "10_10") (pintype "passive"))
    )
    (net (code "72") (name "IRQ5") (class "Default")
      (node (ref "J1") (pin "A8") (pinfunction "A8_A8") (pintype "passive"))
      (node (ref "JP1") (pin "12") (pinfunction "12_12") (pintype "passive"))
    )
    (net (code "73") (name "IRQ6") (class "Default")
      (node (ref "J1") (pin "A9") (pinfunction "A9_A9") (pintype "passive"))
      (node (ref "JP1") (pin "14") (pinfunction "14_14") (pintype "passive"))
    )
    (net (code "74") (name "IRQ7") (class "Default")
      (node (ref "J1") (pin "A10") (pinfunction "A10_A10") (pintype "passive"))
      (node (ref "JP1") (pin "16") (pinfunction "16_16") (pintype "passive"))
    )
    (net (code "75") (name "MEMSEG") (class "Default")
      (node (ref "JP10") (pin "14") (pinfunction "14_14") (pintype "passive"))
    )
    (net (code "76") (name "Net-(IC1A-O)") (class "Default")
      (node (ref "IC1") (pin "3") (pinfunction "O_3") (pintype "output"))
      (node (ref "IC3") (pin "19") (pinfunction "G_19") (pintype "input"))
    )
    (net (code "77") (name "Net-(IC1B-O)") (class "Default")
      (node (ref "IC1") (pin "6") (pinfunction "O_6") (pintype "output"))
      (node (ref "IC4") (pin "19") (pinfunction "G_19") (pintype "input"))
    )
    (net (code "78") (name "Net-(IC2A-Y1)") (class "Default")
      (node (ref "IC2") (pin "18") (pinfunction "Y1_18") (pintype "tri_state"))
      (node (ref "R1") (pin "1") (pinfunction "1_1") (pintype "passive"))
    )
    (net (code "79") (name "Net-(IC2A-Y2)") (class "Default")
      (node (ref "IC2") (pin "17") (pinfunction "Y2_17") (pintype "tri_state"))
      (node (ref "R2") (pin "1") (pinfunction "1_1") (pintype "passive"))
    )
    (net (code "80") (name "Net-(IC2A-Y3)") (class "Default")
      (node (ref "IC2") (pin "16") (pinfunction "Y3_16") (pintype "tri_state"))
      (node (ref "R3") (pin "1") (pinfunction "1_1") (pintype "passive"))
    )
    (net (code "81") (name "Net-(IC2A-Y4)") (class "Default")
      (node (ref "IC2") (pin "15") (pinfunction "Y4_15") (pintype "tri_state"))
      (node (ref "R4") (pin "1") (pinfunction "1_1") (pintype "passive"))
    )
    (net (code "82") (name "Net-(IC2A-Y5)") (class "Default")
      (node (ref "IC2") (pin "14") (pinfunction "Y5_14") (pintype "tri_state"))
      (node (ref "R5") (pin "1") (pinfunction "1_1") (pintype "passive"))
    )
    (net (code "83") (name "Net-(IC2A-Y6)") (class "Default")
      (node (ref "IC2") (pin "13") (pinfunction "Y6_13") (pintype "tri_state"))
      (node (ref "R6") (pin "1") (pinfunction "1_1") (pintype "passive"))
    )
    (net (code "84") (name "Net-(IC2A-Y7)") (class "Default")
      (node (ref "IC2") (pin "12") (pinfunction "Y7_12") (pintype "tri_state"))
      (node (ref "R7") (pin "1") (pinfunction "1_1") (pintype "passive"))
    )
    (net (code "85") (name "Net-(IC2A-Y8)") (class "Default")
      (node (ref "IC2") (pin "11") (pinfunction "Y8_11") (pintype "tri_state"))
      (node (ref "R8") (pin "1") (pinfunction "1_1") (pintype "passive"))
    )
    (net (code "86") (name "Net-(IC6A-Y1)") (class "Default")
      (node (ref "IC6") (pin "18") (pinfunction "Y1_18") (pintype "tri_state"))
      (node (ref "R9") (pin "1") (pinfunction "1_1") (pintype "passive"))
    )
    (net (code "87") (name "Net-(IC6A-Y2)") (class "Default")
      (node (ref "IC6") (pin "17") (pinfunction "Y2_17") (pintype "tri_state"))
      (node (ref "R10") (pin "1") (pinfunction "1_1") (pintype "passive"))
    )
    (net (code "88") (name "Net-(IC6A-Y3)") (class "Default")
      (node (ref "IC6") (pin "16") (pinfunction "Y3_16") (pintype "tri_state"))
      (node (ref "R11") (pin "1") (pinfunction "1_1") (pintype "passive"))
    )
    (net (code "89") (name "Net-(IC6A-Y4)") (class "Default")
      (node (ref "IC6") (pin "15") (pinfunction "Y4_15") (pintype "tri_state"))
      (node (ref "R12") (pin "1") (pinfunction "1_1") (pintype "passive"))
    )
    (net (code "90") (name "Net-(IC6A-Y5)") (class "Default")
      (node (ref "IC6") (pin "14") (pinfunction "Y5_14") (pintype "tri_state"))
      (node (ref "R13") (pin "1") (pinfunction "1_1") (pintype "passive"))
    )
    (net (code "91") (name "Net-(IC6A-Y6)") (class "Default")
      (node (ref "IC6") (pin "13") (pinfunction "Y6_13") (pintype "tri_state"))
      (node (ref "R14") (pin "1") (pinfunction "1_1") (pintype "passive"))
    )
    (net (code "92") (name "Net-(IC6A-Y7)") (class "Default")
      (node (ref "IC6") (pin "12") (pinfunction "Y7_12") (pintype "tri_state"))
      (node (ref "R15") (pin "1") (pinfunction "1_1") (pintype "passive"))
    )
    (net (code "93") (name "Net-(IC6A-Y8)") (class "Default")
      (node (ref "IC6") (pin "11") (pinfunction "Y8_11") (pintype "tri_state"))
      (node (ref "R16") (pin "1") (pinfunction "1_1") (pintype "passive"))
    )
    (net (code "94") (name "Net-(IC9A-D)") (class "Default")
      (node (ref "IC9") (pin "2") (pinfunction "D_2") (pintype "input"))
      (node (ref "IC9") (pin "8") (pinfunction "~{Q}_8") (pintype "output"))
    )
    (net (code "95") (name "Net-(IC10A-CLK)") (class "Default")
      (node (ref "IC10") (pin "11") (pinfunction "CLK_11") (pintype "input"))
      (node (ref "IC10") (pin "3") (pinfunction "CLK_3") (pintype "input"))
      (node (ref "IC9") (pin "11") (pinfunction "CLK_11") (pintype "input"))
      (node (ref "IC9") (pin "3") (pinfunction "CLK_3") (pintype "input"))
      (node (ref "OSC1") (pin "8") (pinfunction "OUT_8") (pintype "output"))
    )
    (net (code "96") (name "Net-(IC10A-D)") (class "Default")
      (node (ref "IC10") (pin "2") (pinfunction "D_2") (pintype "input"))
      (node (ref "IC10") (pin "8") (pinfunction "~{Q}_8") (pintype "output"))
    )
    (net (code "97") (name "Net-(IC10A-Q)") (class "Default")
      (node (ref "IC10") (pin "12") (pinfunction "D_12") (pintype "input"))
      (node (ref "IC10") (pin "5") (pinfunction "Q_5") (pintype "output"))
    )
    (net (code "98") (name "Net-(IC10B-CLR)") (class "Default")
      (node (ref "IC10") (pin "13") (pinfunction "CLR_13") (pintype "input"))
      (node (ref "IC16") (pin "6") (pinfunction "O_6") (pintype "output"))
      (node (ref "IC9") (pin "13") (pinfunction "CLR_13") (pintype "input"))
    )
    (net (code "99") (name "Net-(IC10B-Q)") (class "Default")
      (node (ref "IC10") (pin "9") (pinfunction "Q_9") (pintype "output"))
      (node (ref "IC11") (pin "1") (pinfunction "CLK_1") (pintype "input"))
    )
    (net (code "100") (name "Net-(IC11A-J)") (class "Default")
      (node (ref "IC11") (pin "14") (pinfunction "J_14") (pintype "input"))
      (node (ref "IC11") (pin "3") (pinfunction "K_3") (pintype "input"))
      (node (ref "IC16") (pin "2") (pinfunction "O_2") (pintype "output"))
    )
    (net (code "101") (name "Net-(IC11A-~{Q})") (class "Default")
      (node (ref "IC11") (pin "13") (pinfunction "~{Q}_13") (pintype "output"))
      (node (ref "IC9") (pin "1") (pinfunction "CLR_1") (pintype "input"))
    )
    (net (code "102") (name "Net-(IC12-PBRST)") (class "Default")
      (node (ref "IC12") (pin "1") (pinfunction "PBRST_1") (pintype "input"))
      (node (ref "S1") (pin "1") (pinfunction "S_1") (pintype "passive"))
      (node (ref "S1") (pin "2") (pinfunction "S1_2") (pintype "passive"))
    )
    (net (code "103") (name "Net-(IC12-ST)") (class "Default")
      (node (ref "IC12") (pin "7") (pinfunction "ST_7") (pintype "input"))
      (node (ref "IC13") (pin "2") (pinfunction "I1_2") (pintype "input"))
      (node (ref "IC14") (pin "15") (pinfunction "A3_15") (pintype "input"))
      (node (ref "IC15") (pin "3") (pinfunction "CLK_3") (pintype "input"))
      (node (ref "IC9") (pin "9") (pinfunction "Q_9") (pintype "output"))
    )
    (net (code "104") (name "Net-(IC13A-I0)") (class "Default")
      (node (ref "IC13") (pin "1") (pinfunction "I0_1") (pintype "input"))
      (node (ref "IC13") (pin "4") (pinfunction "I0_4") (pintype "input"))
      (node (ref "IC13") (pin "5") (pinfunction "I1_5") (pintype "input"))
      (node (ref "IC9") (pin "12") (pinfunction "D_12") (pintype "input"))
      (node (ref "IC9") (pin "5") (pinfunction "Q_5") (pintype "output"))
    )
    (net (code "105") (name "Net-(IC13A-O)") (class "Default")
      (node (ref "IC13") (pin "3") (pinfunction "O_3") (pintype "output"))
      (node (ref "IC14") (pin "11") (pinfunction "A1_11") (pintype "input"))
      (node (ref "IC14") (pin "13") (pinfunction "A2_13") (pintype "input"))
    )
    (net (code "106") (name "Net-(IC13B-O)") (class "Default")
      (node (ref "IC13") (pin "10") (pinfunction "I1_10") (pintype "input"))
      (node (ref "IC13") (pin "6") (pinfunction "O_6") (pintype "output"))
      (node (ref "IC13") (pin "9") (pinfunction "I0_9") (pintype "input"))
    )
    (net (code "107") (name "Net-(IC13C-O)") (class "Default")
      (node (ref "IC13") (pin "8") (pinfunction "O_8") (pintype "output"))
      (node (ref "IC14") (pin "2") (pinfunction "A1_2") (pintype "input"))
      (node (ref "IC14") (pin "4") (pinfunction "A2_4") (pintype "input"))
      (node (ref "IC14") (pin "6") (pinfunction "A3_6") (pintype "input"))
      (node (ref "IC14") (pin "8") (pinfunction "A4_8") (pintype "input"))
    )
    (net (code "108") (name "Net-(IC14B-A4)") (class "Default")
      (node (ref "IC14") (pin "17") (pinfunction "A4_17") (pintype "input"))
      (node (ref "IC15") (pin "5") (pinfunction "Q_5") (pintype "output"))
    )
    (net (code "109") (name "Net-(IC15A-D)") (class "Default")
      (node (ref "IC12") (pin "6") (pinfunction "RST_6") (pintype "output"))
      (node (ref "IC15") (pin "2") (pinfunction "D_2") (pintype "input"))
      (node (ref "R19") (pin "1") (pinfunction "1_1") (pintype "passive"))
    )
    (net (code "110") (name "Net-(IC16E-I)") (class "Default")
      (node (ref "C1") (pin "+") (pinfunction "+_+") (pintype "passive"))
      (node (ref "IC16") (pin "3") (pinfunction "I_3") (pintype "input"))
      (node (ref "R17") (pin "1") (pinfunction "1_1") (pintype "passive"))
    )
    (net (code "111") (name "Net-(IC16E-O)") (class "Default")
      (node (ref "IC16") (pin "4") (pinfunction "O_4") (pintype "output"))
      (node (ref "IC16") (pin "5") (pinfunction "I_5") (pintype "input"))
    )
    (net (code "112") (name "Net-(LED1-PadA)") (class "Default")
      (node (ref "LED1") (pin "A") (pinfunction "A_A") (pintype "passive"))
      (node (ref "R18") (pin "1") (pinfunction "1_1") (pintype "passive"))
    )
    (net (code "113") (name "PABUS12") (class "Default")
      (node (ref "J1") (pin "C15") (pinfunction "C15_C15") (pintype "passive"))
      (node (ref "JP5") (pin "1") (pinfunction "1_1") (pintype "passive"))
    )
    (net (code "114") (name "PABUS13") (class "Default")
      (node (ref "J1") (pin "A15") (pinfunction "A15_A15") (pintype "passive"))
      (node (ref "JP5") (pin "2") (pinfunction "2_2") (pintype "passive"))
    )
    (net (code "115") (name "PABUS14") (class "Default")
      (node (ref "J1") (pin "C16") (pinfunction "C16_C16") (pintype "passive"))
      (node (ref "JP5") (pin "3") (pinfunction "3_3") (pintype "passive"))
    )
    (net (code "116") (name "PABUS15") (class "Default")
      (node (ref "J1") (pin "A16") (pinfunction "A16_A16") (pintype "passive"))
      (node (ref "JP5") (pin "4") (pinfunction "4_4") (pintype "passive"))
    )
    (net (code "117") (name "PABUS16") (class "Default")
      (node (ref "J1") (pin "C17") (pinfunction "C17_C17") (pintype "passive"))
      (node (ref "JP5") (pin "5") (pinfunction "5_5") (pintype "passive"))
    )
    (net (code "118") (name "PABUS17") (class "Default")
      (node (ref "J1") (pin "A17") (pinfunction "A17_A17") (pintype "passive"))
      (node (ref "JP5") (pin "6") (pinfunction "6_6") (pintype "passive"))
    )
    (net (code "119") (name "PABUS18") (class "Default")
      (node (ref "J1") (pin "C18") (pinfunction "C18_C18") (pintype "passive"))
      (node (ref "JP5") (pin "7") (pinfunction "7_7") (pintype "passive"))
    )
    (net (code "120") (name "PABUS19") (class "Default")
      (node (ref "J1") (pin "A18") (pinfunction "A18_A18") (pintype "passive"))
      (node (ref "JP5") (pin "8") (pinfunction "8_8") (pintype "passive"))
    )
    (net (code "121") (name "PABUS20") (class "Default")
      (node (ref "J1") (pin "C19") (pinfunction "C19_C19") (pintype "passive"))
      (node (ref "JP5") (pin "9") (pinfunction "9_9") (pintype "passive"))
    )
    (net (code "122") (name "PABUS21") (class "Default")
      (node (ref "J1") (pin "A19") (pinfunction "A19_A19") (pintype "passive"))
      (node (ref "JP5") (pin "10") (pinfunction "10_10") (pintype "passive"))
    )
    (net (code "123") (name "PROT") (class "Default")
      (node (ref "JP10") (pin "21") (pinfunction "21_21") (pintype "passive"))
    )
    (net (code "124") (name "RBUS0") (class "Default")
      (node (ref "IC17") (pin "18") (pinfunction "Y1_18") (pintype "tri_state"))
      (node (ref "JP4") (pin "1") (pinfunction "1_1") (pintype "passive"))
    )
    (net (code "125") (name "RBUS1") (class "Default")
      (node (ref "IC17") (pin "17") (pinfunction "Y2_17") (pintype "tri_state"))
      (node (ref "JP4") (pin "2") (pinfunction "2_2") (pintype "passive"))
    )
    (net (code "126") (name "RBUS2") (class "Default")
      (node (ref "IC17") (pin "16") (pinfunction "Y3_16") (pintype "tri_state"))
      (node (ref "JP4") (pin "3") (pinfunction "3_3") (pintype "passive"))
    )
    (net (code "127") (name "RBUS3") (class "Default")
      (node (ref "IC17") (pin "15") (pinfunction "Y4_15") (pintype "tri_state"))
      (node (ref "JP4") (pin "4") (pinfunction "4_4") (pintype "passive"))
    )
    (net (code "128") (name "RBUS4") (class "Default")
      (node (ref "IC17") (pin "14") (pinfunction "Y5_14") (pintype "tri_state"))
      (node (ref "JP4") (pin "5") (pinfunction "5_5") (pintype "passive"))
    )
    (net (code "129") (name "RBUS5") (class "Default")
      (node (ref "IC17") (pin "13") (pinfunction "Y6_13") (pintype "tri_state"))
      (node (ref "JP4") (pin "6") (pinfunction "6_6") (pintype "passive"))
    )
    (net (code "130") (name "RBUS6") (class "Default")
      (node (ref "IC17") (pin "12") (pinfunction "Y7_12") (pintype "tri_state"))
      (node (ref "JP4") (pin "7") (pinfunction "7_7") (pintype "passive"))
    )
    (net (code "131") (name "RBUS7") (class "Default")
      (node (ref "IC17") (pin "11") (pinfunction "Y8_11") (pintype "tri_state"))
      (node (ref "JP4") (pin "8") (pinfunction "8_8") (pintype "passive"))
    )
    (net (code "132") (name "RBUS8") (class "Default")
      (node (ref "IC18") (pin "18") (pinfunction "Y1_18") (pintype "tri_state"))
      (node (ref "JP4") (pin "9") (pinfunction "9_9") (pintype "passive"))
    )
    (net (code "133") (name "RBUS9") (class "Default")
      (node (ref "IC18") (pin "17") (pinfunction "Y2_17") (pintype "tri_state"))
      (node (ref "JP4") (pin "10") (pinfunction "10_10") (pintype "passive"))
    )
    (net (code "134") (name "RBUS10") (class "Default")
      (node (ref "IC18") (pin "16") (pinfunction "Y3_16") (pintype "tri_state"))
      (node (ref "JP4") (pin "11") (pinfunction "11_11") (pintype "passive"))
    )
    (net (code "135") (name "RBUS11") (class "Default")
      (node (ref "IC18") (pin "15") (pinfunction "Y4_15") (pintype "tri_state"))
      (node (ref "JP4") (pin "12") (pinfunction "12_12") (pintype "passive"))
    )
    (net (code "136") (name "RBUS12") (class "Default")
      (node (ref "IC18") (pin "14") (pinfunction "Y5_14") (pintype "tri_state"))
      (node (ref "JP4") (pin "13") (pinfunction "13_13") (pintype "passive"))
    )
    (net (code "137") (name "RBUS13") (class "Default")
      (node (ref "IC18") (pin "13") (pinfunction "Y6_13") (pintype "tri_state"))
      (node (ref "JP4") (pin "14") (pinfunction "14_14") (pintype "passive"))
    )
    (net (code "138") (name "RBUS14") (class "Default")
      (node (ref "IC18") (pin "12") (pinfunction "Y7_12") (pintype "tri_state"))
      (node (ref "JP4") (pin "15") (pinfunction "15_15") (pintype "passive"))
    )
    (net (code "139") (name "RBUS15") (class "Default")
      (node (ref "IC18") (pin "11") (pinfunction "Y8_11") (pintype "tri_state"))
      (node (ref "JP4") (pin "16") (pinfunction "16_16") (pintype "passive"))
    )
    (net (code "140") (name "RST") (class "Default")
      (node (ref "IC15") (pin "6") (pinfunction "~{Q}_6") (pintype "output"))
      (node (ref "JP10") (pin "9") (pinfunction "9_9") (pintype "passive"))
    )
    (net (code "141") (name "SP_DIR") (class "Default")
      (node (ref "JP10") (pin "20") (pinfunction "20_20") (pintype "passive"))
    )
    (net (code "142") (name "unconnected-(IC1C-O-Pad8)") (class "Default")
      (node (ref "IC1") (pin "8") (pinfunction "O_8") (pintype "output"))
    )
    (net (code "143") (name "unconnected-(IC1D-O-Pad11)") (class "Default")
      (node (ref "IC1") (pin "11") (pinfunction "O_11") (pintype "output"))
    )
    (net (code "144") (name "unconnected-(IC9A-~{Q}-Pad6)") (class "Default")
      (node (ref "IC9") (pin "6") (pinfunction "~{Q}_6") (pintype "output"))
    )
    (net (code "145") (name "unconnected-(IC10A-~{Q}-Pad6)") (class "Default")
      (node (ref "IC10") (pin "6") (pinfunction "~{Q}_6") (pintype "output"))
    )
    (net (code "146") (name "unconnected-(IC11A-Q-Pad12)") (class "Default")
      (node (ref "IC11") (pin "12") (pinfunction "Q_12") (pintype "output"))
    )
    (net (code "147") (name "unconnected-(IC11B-Q-Pad9)") (class "Default")
      (node (ref "IC11") (pin "9") (pinfunction "Q_9") (pintype "output"))
    )
    (net (code "148") (name "unconnected-(IC11B-~{Q}-Pad8)") (class "Default")
      (node (ref "IC11") (pin "8") (pinfunction "~{Q}_8") (pintype "output"))
    )
    (net (code "149") (name "unconnected-(IC12-RST-Pad5)") (class "Default")
      (node (ref "IC12") (pin "5") (pinfunction "RST_5") (pintype "output"))
    )
    (net (code "150") (name "unconnected-(IC12-TD-Pad2)") (class "Default")
      (node (ref "IC12") (pin "2") (pinfunction "TD_2") (pintype "input"))
    )
    (net (code "151") (name "unconnected-(IC13D-O-Pad11)") (class "Default")
      (node (ref "IC13") (pin "11") (pinfunction "O_11") (pintype "output"))
    )
    (net (code "152") (name "unconnected-(IC15B-Q-Pad9)") (class "Default")
      (node (ref "IC15") (pin "9") (pinfunction "Q_9") (pintype "output"))
    )
    (net (code "153") (name "unconnected-(IC15B-~{Q}-Pad8)") (class "Default")
      (node (ref "IC15") (pin "8") (pinfunction "~{Q}_8") (pintype "output"))
    )
    (net (code "154") (name "unconnected-(IC16A-O-Pad12)") (class "Default")
      (node (ref "IC16") (pin "12") (pinfunction "O_12") (pintype "output"))
    )
    (net (code "155") (name "unconnected-(IC16B-O-Pad10)") (class "Default")
      (node (ref "IC16") (pin "10") (pinfunction "O_10") (pintype "output"))
    )
    (net (code "156") (name "unconnected-(IC16C-O-Pad8)") (class "Default")
      (node (ref "IC16") (pin "8") (pinfunction "O_8") (pintype "output"))
    )
    (net (code "157") (name "unconnected-(J1-PadA11)") (class "Default")
      (node (ref "J1") (pin "A11") (pinfunction "A11_A11") (pintype "passive"))
    )
    (net (code "158") (name "unconnected-(J1-PadA12)") (class "Default")
      (node (ref "J1") (pin "A12") (pinfunction "A12_A12") (pintype "passive"))
    )
    (net (code "159") (name "unconnected-(J1-PadA13)") (class "Default")
      (node (ref "J1") (pin "A13") (pinfunction "A13_A13") (pintype "passive"))
    )
    (net (code "160") (name "unconnected-(J1-PadA14)") (class "Default")
      (node (ref "J1") (pin "A14") (pinfunction "A14_A14") (pintype "passive"))
    )
    (net (code "161") (name "unconnected-(J1-PadA21)") (class "Default")
      (node (ref "J1") (pin "A21") (pinfunction "A21_A21") (pintype "passive"))
    )
    (net (code "162") (name "unconnected-(J1-PadC12)") (class "Default")
      (node (ref "J1") (pin "C12") (pinfunction "C12_C12") (pintype "passive"))
    )
    (net (code "163") (name "unconnected-(J1-PadC13)") (class "Default")
      (node (ref "J1") (pin "C13") (pinfunction "C13_C13") (pintype "passive"))
    )
    (net (code "164") (name "unconnected-(J1-PadC14)") (class "Default")
      (node (ref "J1") (pin "C14") (pinfunction "C14_C14") (pintype "passive"))
    )
    (net (code "165") (name "unconnected-(J1-PadC20)") (class "Default")
      (node (ref "J1") (pin "C20") (pinfunction "C20_C20") (pintype "passive"))
    )
    (net (code "166") (name "unconnected-(J1-PadC21)") (class "Default")
      (node (ref "J1") (pin "C21") (pinfunction "C21_C21") (pintype "passive"))
    )
    (net (code "167") (name "unconnected-(OSC1-TS-Pad1)") (class "Default")
      (node (ref "OSC1") (pin "1") (pinfunction "TS_1") (pintype "passive"))
    )
    (net (code "168") (name "{slash}ALUHI2MEM") (class "Default")
      (node (ref "IC1") (pin "1") (pinfunction "I0_1") (pintype "input"))
      (node (ref "IC3") (pin "1") (pinfunction "DIR_1") (pintype "input"))
      (node (ref "JP10") (pin "25") (pinfunction "25_25") (pintype "passive"))
    )
    (net (code "169") (name "{slash}ALULO2MEM") (class "Default")
      (node (ref "IC1") (pin "4") (pinfunction "I0_4") (pintype "input"))
      (node (ref "IC4") (pin "1") (pinfunction "DIR_1") (pintype "input"))
      (node (ref "JP10") (pin "29") (pinfunction "29_29") (pintype "passive"))
    )
    (net (code "170") (name "{slash}BUSIFCEN") (class "Default")
      (node (ref "JP10") (pin "5") (pinfunction "5_5") (pintype "passive"))
    )
    (net (code "171") (name "{slash}CNTSP") (class "Default")
      (node (ref "JP10") (pin "3") (pinfunction "3_3") (pintype "passive"))
    )
    (net (code "172") (name "{slash}ENABUS") (class "Default")
      (node (ref "IC17") (pin "1") (pinfunction "G1_1") (pintype "input"))
      (node (ref "IC17") (pin "19") (pinfunction "G2_19") (pintype "input"))
      (node (ref "IC18") (pin "1") (pinfunction "G1_1") (pintype "input"))
      (node (ref "IC18") (pin "19") (pinfunction "G2_19") (pintype "input"))
      (node (ref "JP10") (pin "22") (pinfunction "22_22") (pintype "passive"))
    )
    (net (code "173") (name "{slash}ENMEM") (class "Default")
      (node (ref "JP10") (pin "16") (pinfunction "16_16") (pintype "passive"))
    )
    (net (code "174") (name "{slash}ENMEMX") (class "Default")
      (node (ref "J1") (pin "C22") (pinfunction "C22_C22") (pintype "passive"))
      (node (ref "JP5") (pin "11") (pinfunction "11_11") (pintype "passive"))
    )
    (net (code "175") (name "{slash}FI") (class "Default")
      (node (ref "JP10") (pin "32") (pinfunction "32_32") (pintype "passive"))
    )
    (net (code "176") (name "{slash}FP") (class "Default")
      (node (ref "JP10") (pin "34") (pinfunction "34_34") (pintype "passive"))
    )
    (net (code "177") (name "{slash}FS") (class "Default")
      (node (ref "JP10") (pin "30") (pinfunction "30_30") (pintype "passive"))
    )
    (net (code "178") (name "{slash}INCPC") (class "Default")
      (node (ref "JP10") (pin "1") (pinfunction "1_1") (pintype "passive"))
    )
    (net (code "179") (name "{slash}IO") (class "Default")
      (node (ref "IC16") (pin "1") (pinfunction "I_1") (pintype "input"))
      (node (ref "J1") (pin "C11") (pinfunction "C11_C11") (pintype "passive"))
      (node (ref "JP10") (pin "35") (pinfunction "35_35") (pintype "passive"))
    )
    (net (code "180") (name "{slash}LATCHFLAGS") (class "Default")
      (node (ref "JP10") (pin "12") (pinfunction "12_12") (pintype "passive"))
    )
    (net (code "181") (name "{slash}LDMEM") (class "Default")
      (node (ref "JP10") (pin "15") (pinfunction "15_15") (pintype "passive"))
    )
    (net (code "182") (name "{slash}LDMEMX") (class "Default")
      (node (ref "J1") (pin "A22") (pinfunction "A22_A22") (pintype "passive"))
      (node (ref "JP5") (pin "12") (pinfunction "12_12") (pintype "passive"))
    )
    (net (code "183") (name "{slash}LOAD_IR") (class "Default")
      (node (ref "JP10") (pin "26") (pinfunction "26_26") (pintype "passive"))
    )
    (net (code "184") (name "{slash}MEM2ALUHI") (class "Default")
      (node (ref "IC1") (pin "2") (pinfunction "I1_2") (pintype "input"))
      (node (ref "JP10") (pin "27") (pinfunction "27_27") (pintype "passive"))
    )
    (net (code "185") (name "{slash}MEM2ALULO") (class "Default")
      (node (ref "IC1") (pin "5") (pinfunction "I1_5") (pintype "input"))
      (node (ref "IC19") (pin "1") (pinfunction "G1_1") (pintype "input"))
      (node (ref "IC19") (pin "19") (pinfunction "G2_19") (pintype "input"))
      (node (ref "JP10") (pin "31") (pinfunction "31_31") (pintype "passive"))
    )
    (net (code "186") (name "{slash}MEMOP") (class "Default")
      (node (ref "JP10") (pin "11") (pinfunction "11_11") (pintype "passive"))
    )
    (net (code "187") (name "{slash}NP_FAULT") (class "Default")
      (node (ref "JP10") (pin "36") (pinfunction "36_36") (pintype "passive"))
    )
    (net (code "188") (name "{slash}RST") (class "Default")
      (node (ref "IC11") (pin "2") (pinfunction "CL_2") (pintype "input"))
      (node (ref "IC14") (pin "3") (pinfunction "Y4_3") (pintype "tri_state"))
      (node (ref "J1") (pin "A20") (pinfunction "A20_A20") (pintype "passive"))
      (node (ref "JP10") (pin "7") (pinfunction "7_7") (pintype "passive"))
    )
    (net (code "189") (name "{slash}WR_FAULT") (class "Default")
      (node (ref "JP10") (pin "33") (pinfunction "33_33") (pintype "passive"))
    )
  )
)
